# 1_Battery.net
KiCad netlist of a schematic drawn in Altium Designer
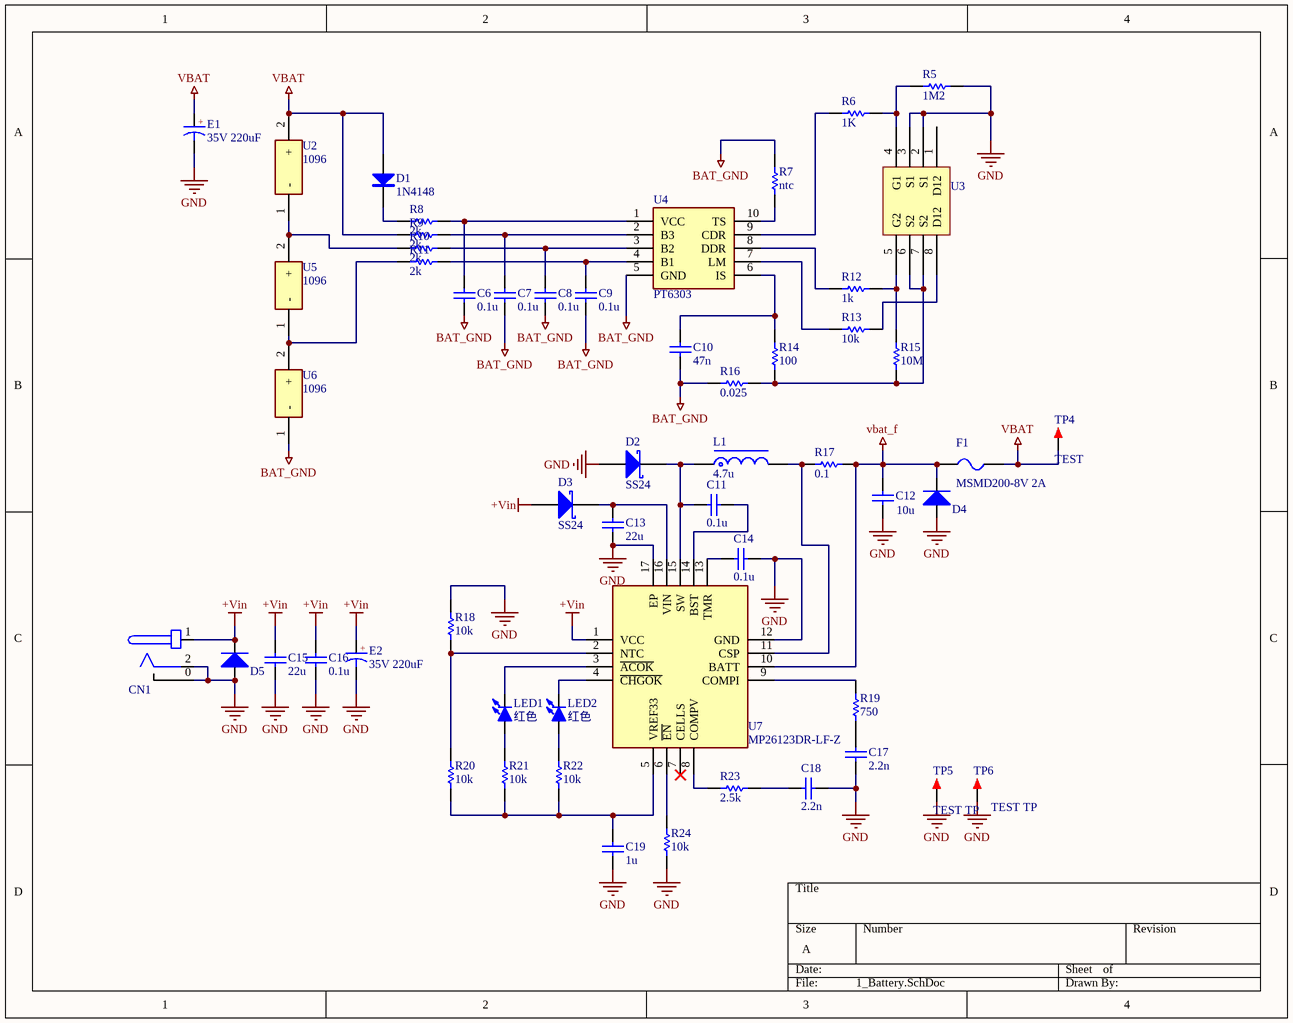
[diagram p0: 1_Battery.SchDoc]

(export (version "E")
  (design (tool "Eeschema 10.0.6"))
  (components
    (comp (ref "C6")
      (value "0.1u")
      (footprint "CAP_0603_SMD")
      (description "Capacitor, 0603, SMD")
      (fields (field (name "PUBLISHER") "Altium Limited"))
      (libsource (lib "myRLC") (part "CAP_0603_SMD"))
    )
    (comp (ref "C7")
      (value "0.1u")
      (footprint "CAP_0603_SMD")
      (description "Capacitor, 0603, SMD")
      (fields (field (name "PUBLISHER") "Altium Limited"))
      (libsource (lib "myRLC") (part "CAP_0603_SMD"))
    )
    (comp (ref "C8")
      (value "0.1u")
      (footprint "CAP_0603_SMD")
      (description "Capacitor, 0603, SMD")
      (fields (field (name "PUBLISHER") "Altium Limited"))
      (libsource (lib "myRLC") (part "CAP_0603_SMD"))
    )
    (comp (ref "C9")
      (value "0.1u")
      (footprint "CAP_0603_SMD")
      (description "Capacitor, 0603, SMD")
      (fields (field (name "PUBLISHER") "Altium Limited"))
      (libsource (lib "myRLC") (part "CAP_0603_SMD"))
    )
    (comp (ref "C10")
      (value "47n")
      (footprint "CAP_0603_SMD")
      (description "Capacitor, 0603, SMD")
      (fields (field (name "PUBLISHER") "Altium Limited"))
      (libsource (lib "myRLC") (part "CAP_0603_SMD"))
    )
    (comp (ref "C11")
      (value "0.1u")
      (footprint "CAP_0603_SMD")
      (description "Capacitor, 0603, SMD")
      (fields (field (name "PUBLISHER") "Altium Limited"))
      (libsource (lib "myRLC") (part "CAP_0603_SMD"))
    )
    (comp (ref "C12")
      (value "10u")
      (footprint "C1206_L")
      (description "贴片电容")
      (libsource (lib "0.1 - 电阻-电容-电感-电位器") (part "C"))
    )
    (comp (ref "C13")
      (value "22u")
      (footprint "C1812_L")
      (description "贴片电容")
      (libsource (lib "0.1 - 电阻-电容-电感-电位器") (part "C"))
    )
    (comp (ref "C14")
      (value "0.1u")
      (footprint "CAP_0603_SMD")
      (description "Capacitor, 0603, SMD")
      (fields (field (name "PUBLISHER") "Altium Limited"))
      (libsource (lib "myRLC") (part "CAP_0603_SMD"))
    )
    (comp (ref "C15")
      (value "22u")
      (footprint "C1812_L")
      (description "贴片电容")
      (libsource (lib "0.1 - 电阻-电容-电感-电位器") (part "C"))
    )
    (comp (ref "C16")
      (value "0.1u")
      (footprint "CAP_0603_SMD")
      (description "Capacitor, 0603, SMD")
      (fields (field (name "PUBLISHER") "Altium Limited"))
      (libsource (lib "myRLC") (part "CAP_0603_SMD"))
    )
    (comp (ref "C17")
      (value "2.2n")
      (footprint "CAP_0603_SMD")
      (description "Capacitor, 0603, SMD")
      (fields (field (name "PUBLISHER") "Altium Limited"))
      (libsource (lib "myRLC") (part "CAP_0603_SMD"))
    )
    (comp (ref "C18")
      (value "2.2n")
      (footprint "CAP_0603_SMD")
      (description "Capacitor, 0603, SMD")
      (fields (field (name "PUBLISHER") "Altium Limited"))
      (libsource (lib "myRLC") (part "CAP_0603_SMD"))
    )
    (comp (ref "C19")
      (value "1u")
      (footprint "CAP_0603_SMD")
      (description "Capacitor, 0603, SMD")
      (fields (field (name "PUBLISHER") "Altium Limited"))
      (libsource (lib "myRLC") (part "CAP_0603_SMD"))
    )
    (comp (ref "CN1")
      (value "PWR5.5x2.1_HP")
      (footprint "PWR5.5x2.1_HP")
      (description "DC Socket, 5.5x2.1, High-power")
      (libsource (lib "myConnectors") (part "PWR5.5x2.1_HP"))
    )
    (comp (ref "D1")
      (value "1N4148")
      (footprint "SOD-323")
      (description "开关二极管")
      (libsource (lib "0.2 - 二极管-TVS-整流桥") (part "1N4148"))
    )
    (comp (ref "D2")
      (value "SS24")
      (footprint "SMB")
      (description "肖特基二极管")
      (libsource (lib "0.2 - 二极管-TVS-整流桥") (part "SS24"))
    )
    (comp (ref "D3")
      (value "SS24")
      (footprint "SMB")
      (description "肖特基二极管")
      (libsource (lib "0.2 - 二极管-TVS-整流桥") (part "SS24"))
    )
    (comp (ref "D4")
      (value "TVS")
      (footprint "SMA")
      (description "TVS通用")
      (libsource (lib "0.2 - 二极管-TVS-整流桥") (part "TVS"))
    )
    (comp (ref "D5")
      (value "TVS")
      (footprint "SMA")
      (description "TVS通用")
      (libsource (lib "0.2 - 二极管-TVS-整流桥") (part "TVS"))
    )
    (comp (ref "E1")
      (value "35V 220uF")
      (footprint "CE E(8*10.2)")
      (description "贴片电解电容")
      (libsource (lib "0.1 - 电阻-电容-电感-电位器") (part "CE_SMD"))
    )
    (comp (ref "E2")
      (value "35V 220uF")
      (footprint "CE E(8*10.2)")
      (description "贴片电解电容")
      (libsource (lib "0.1 - 电阻-电容-电感-电位器") (part "CE_SMD"))
    )
    (comp (ref "F1")
      (value "MSMD200-8V 2A")
      (footprint "FU 1812")
      (description "贴片保险丝")
      (libsource (lib "0.5 - 保险丝-晶振-光耦") (part "FU"))
    )
    (comp (ref "L1")
      (value "4.7u")
      (footprint "L-SMD-0630")
      (description "一体成型电感")
      (libsource (lib "0.1 - 电阻-电容-电感-电位器") (part "L-Molding Choke"))
    )
    (comp (ref "LED1")
      (value "红色")
      (footprint "LED0603_Y")
      (description "贴片LED")
      (libsource (lib "0.3 - LED发光二极管") (part "LED-SMD"))
    )
    (comp (ref "LED2")
      (value "红色")
      (footprint "LED0603_Y")
      (description "贴片LED")
      (libsource (lib "0.3 - LED发光二极管") (part "LED-SMD"))
    )
    (comp (ref "R5")
      (value "1M2")
      (footprint "RES_0603_SMD")
      (description "Resistor, 0603, SMD")
      (fields (field (name "PUBLISHER") "Altium Limited"))
      (libsource (lib "myRLC") (part "RES_0603_SMD"))
    )
    (comp (ref "R6")
      (value "1K")
      (footprint "RES_0603_SMD")
      (description "Resistor, 0603, SMD")
      (fields (field (name "PUBLISHER") "Altium Limited"))
      (libsource (lib "myRLC") (part "RES_0603_SMD"))
    )
    (comp (ref "R7")
      (value "ntc")
      (footprint "RES_0603_SMD")
      (description "Resistor, 0603, SMD")
      (fields (field (name "PUBLISHER") "Altium Limited"))
      (libsource (lib "myRLC") (part "RES_0603_SMD"))
    )
    (comp (ref "R8")
      (value "2k")
      (footprint "RES_0603_SMD")
      (description "Resistor, 0603, SMD")
      (fields (field (name "PUBLISHER") "Altium Limited"))
      (libsource (lib "myRLC") (part "RES_0603_SMD"))
    )
    (comp (ref "R9")
      (value "2k")
      (footprint "RES_0603_SMD")
      (description "Resistor, 0603, SMD")
      (fields (field (name "PUBLISHER") "Altium Limited"))
      (libsource (lib "myRLC") (part "RES_0603_SMD"))
    )
    (comp (ref "R10")
      (value "2k")
      (footprint "RES_0603_SMD")
      (description "Resistor, 0603, SMD")
      (fields (field (name "PUBLISHER") "Altium Limited"))
      (libsource (lib "myRLC") (part "RES_0603_SMD"))
    )
    (comp (ref "R11")
      (value "2k")
      (footprint "RES_0603_SMD")
      (description "Resistor, 0603, SMD")
      (fields (field (name "PUBLISHER") "Altium Limited"))
      (libsource (lib "myRLC") (part "RES_0603_SMD"))
    )
    (comp (ref "R12")
      (value "1k")
      (footprint "RES_0603_SMD")
      (description "Resistor, 0603, SMD")
      (fields (field (name "PUBLISHER") "Altium Limited"))
      (libsource (lib "myRLC") (part "RES_0603_SMD"))
    )
    (comp (ref "R13")
      (value "10k")
      (footprint "RES_0603_SMD")
      (description "Resistor, 0603, SMD")
      (fields (field (name "PUBLISHER") "Altium Limited"))
      (libsource (lib "myRLC") (part "RES_0603_SMD"))
    )
    (comp (ref "R14")
      (value "100")
      (footprint "RES_0603_SMD")
      (description "Resistor, 0603, SMD")
      (fields (field (name "PUBLISHER") "Altium Limited"))
      (libsource (lib "myRLC") (part "RES_0603_SMD"))
    )
    (comp (ref "R15")
      (value "10M")
      (footprint "RES_0603_SMD")
      (description "Resistor, 0603, SMD")
      (fields (field (name "PUBLISHER") "Altium Limited"))
      (libsource (lib "myRLC") (part "RES_0603_SMD"))
    )
    (comp (ref "R16")
      (value "0.025")
      (footprint "RES_1206_SMD")
      (description "Resistor, 1206, SMD")
      (fields (field (name "PUBLISHER") "Altium Limited"))
      (libsource (lib "myRLC") (part "RES_1206_SMD"))
    )
    (comp (ref "R17")
      (value "0.1")
      (footprint "RES_1206_SMD")
      (description "Resistor, 1206, SMD")
      (fields (field (name "PUBLISHER") "Altium Limited"))
      (libsource (lib "myRLC") (part "RES_1206_SMD"))
    )
    (comp (ref "R18")
      (value "10k")
      (footprint "RES_0603_SMD")
      (description "Resistor, 0603, SMD")
      (fields (field (name "PUBLISHER") "Altium Limited"))
      (libsource (lib "myRLC") (part "RES_0603_SMD"))
    )
    (comp (ref "R19")
      (value "750")
      (footprint "RES_0603_SMD")
      (description "Resistor, 0603, SMD")
      (fields (field (name "PUBLISHER") "Altium Limited"))
      (libsource (lib "myRLC") (part "RES_0603_SMD"))
    )
    (comp (ref "R20")
      (value "10k")
      (footprint "RES_0603_SMD")
      (description "Resistor, 0603, SMD")
      (fields (field (name "PUBLISHER") "Altium Limited"))
      (libsource (lib "myRLC") (part "RES_0603_SMD"))
    )
    (comp (ref "R21")
      (value "10k")
      (footprint "RES_0603_SMD")
      (description "Resistor, 0603, SMD")
      (fields (field (name "PUBLISHER") "Altium Limited"))
      (libsource (lib "myRLC") (part "RES_0603_SMD"))
    )
    (comp (ref "R22")
      (value "10k")
      (footprint "RES_0603_SMD")
      (description "Resistor, 0603, SMD")
      (fields (field (name "PUBLISHER") "Altium Limited"))
      (libsource (lib "myRLC") (part "RES_0603_SMD"))
    )
    (comp (ref "R23")
      (value "2.5k")
      (footprint "RES_0603_SMD")
      (description "Resistor, 0603, SMD")
      (fields (field (name "PUBLISHER") "Altium Limited"))
      (libsource (lib "myRLC") (part "RES_0603_SMD"))
    )
    (comp (ref "R24")
      (value "10k")
      (footprint "RES_0603_SMD")
      (description "Resistor, 0603, SMD")
      (fields (field (name "PUBLISHER") "Altium Limited"))
      (libsource (lib "myRLC") (part "RES_0603_SMD"))
    )
    (comp (ref "TP4")
      (value "TEST")
      (footprint "TEST 1.2")
      (description "测试点")
      (libsource (lib "0.7 - 常用按键-开关-蜂鸣器-电池-测试点") (part "TEST"))
    )
    (comp (ref "TP5")
      (value "TEST TP")
      (footprint "TEST TP1.4_BK")
      (description "测试环")
      (libsource (lib "0.7 - 常用按键-开关-蜂鸣器-电池-测试点") (part "TEST TP"))
    )
    (comp (ref "TP6")
      (value "TEST TP")
      (footprint "TEST TP1.4_BK")
      (description "测试环")
      (libsource (lib "0.7 - 常用按键-开关-蜂鸣器-电池-测试点") (part "TEST TP"))
    )
    (comp (ref "U2")
      (value "1096")
      (footprint "TKY:1096")
      (description "Undefined or Miscellaneous")
      (fields (field (name "MOUSER PART NUMBER") "534-1096"))
      (libsource (lib "") (part "1096_1"))
    )
    (comp (ref "U3")
      (value "FS8205A TSSOP-8")
      (footprint "IC_TSSOP-8")
      (description "Dual N-Channel Enhancement Mode Power MOSFET")
      (libsource (lib "myICs") (part "FS8205A TSSOP-8"))
    )
    (comp (ref "U4")
      (value "PT6303")
      (footprint "TKY:SOP50P490X110-10N")
      (description "Integrated Circuit")
      (fields (field (name "ARROW PART NUMBER") "AD4001BRMZ"))
      (libsource (lib "TKY") (part "PT6303"))
    )
    (comp (ref "U5")
      (value "1096")
      (footprint "TKY:1096")
      (description "Undefined or Miscellaneous")
      (fields (field (name "MOUSER PART NUMBER") "534-1096"))
      (libsource (lib "TKY") (part "1096"))
    )
    (comp (ref "U6")
      (value "1096")
      (footprint "TKY:1096")
      (description "Undefined or Miscellaneous")
      (fields (field (name "MOUSER PART NUMBER") "534-1096"))
      (libsource (lib "TKY") (part "1096"))
    )
    (comp (ref "U7")
      (value "MP26123DR-LF-Z")
      (footprint "TKY:QFN65P400X400X100-17N-D")
      (description "Integrated Circuit")
      (fields (field (name "MOUSER PART NUMBER") "946-MP26123DRLFZ"))
      (libsource (lib "TKY") (part "MP26123DR-LF-Z"))
    )
  )
  (nets
    (net (code "1") (name "+Vin") (class "Default")
      (node (ref "C15") (pin "2") (pinfunction "2_2") (pintype "passive"))
      (node (ref "C16") (pin "2") (pinfunction "2_2") (pintype "passive"))
      (node (ref "CN1") (pin "1") (pinfunction "+_1") (pintype "passive"))
      (node (ref "D3") (pin "1") (pinfunction "A_1") (pintype "passive"))
      (node (ref "D5") (pin "2") (pinfunction "K_2") (pintype "passive"))
      (node (ref "E2") (pin "1") (pinfunction "1_1") (pintype "passive"))
      (node (ref "U7") (pin "1") (pinfunction "VCC_1") (pintype "passive"))
    )
    (net (code "2") (name "BAT_GND") (class "Default")
      (node (ref "C10") (pin "2") (pinfunction "2_2") (pintype "passive"))
      (node (ref "C6") (pin "2") (pinfunction "2_2") (pintype "passive"))
      (node (ref "C7") (pin "2") (pinfunction "2_2") (pintype "passive"))
      (node (ref "C8") (pin "2") (pinfunction "2_2") (pintype "passive"))
      (node (ref "C9") (pin "2") (pinfunction "2_2") (pintype "passive"))
      (node (ref "R16") (pin "1") (pinfunction "1_1") (pintype "passive"))
      (node (ref "R7") (pin "1") (pinfunction "1_1") (pintype "passive"))
      (node (ref "U4") (pin "5") (pinfunction "GND_5") (pintype "passive"))
      (node (ref "U6") (pin "1") (pinfunction "-_1") (pintype "passive"))
    )
    (net (code "3") (name "GND") (class "Default")
      (node (ref "C12") (pin "1") (pinfunction "1_1") (pintype "passive"))
      (node (ref "C13") (pin "1") (pinfunction "1_1") (pintype "passive"))
      (node (ref "C14") (pin "2") (pinfunction "2_2") (pintype "passive"))
      (node (ref "C15") (pin "1") (pinfunction "1_1") (pintype "passive"))
      (node (ref "C16") (pin "1") (pinfunction "1_1") (pintype "passive"))
      (node (ref "C17") (pin "1") (pinfunction "1_1") (pintype "passive"))
      (node (ref "C18") (pin "1") (pinfunction "1_1") (pintype "passive"))
      (node (ref "C19") (pin "2") (pinfunction "2_2") (pintype "passive"))
      (node (ref "CN1") (pin "0") (pinfunction "SHIELD_0") (pintype "passive"))
      (node (ref "CN1") (pin "2") (pinfunction "GND_2") (pintype "passive"))
      (node (ref "D2") (pin "1") (pinfunction "A_1") (pintype "passive"))
      (node (ref "D4") (pin "1") (pinfunction "A_1") (pintype "passive"))
      (node (ref "D5") (pin "1") (pinfunction "A_1") (pintype "passive"))
      (node (ref "E1") (pin "2") (pinfunction "2_2") (pintype "passive"))
      (node (ref "E2") (pin "2") (pinfunction "2_2") (pintype "passive"))
      (node (ref "R18") (pin "2") (pinfunction "2_2") (pintype "passive"))
      (node (ref "R24") (pin "2") (pinfunction "2_2") (pintype "passive"))
      (node (ref "R5") (pin "1") (pinfunction "1_1") (pintype "passive"))
      (node (ref "TP5") (pin "1") (pinfunction "1_1") (pintype "passive"))
      (node (ref "TP6") (pin "1") (pinfunction "1_1") (pintype "passive"))
      (node (ref "U3") (pin "2") (pinfunction "S1_2") (pintype "passive"))
      (node (ref "U3") (pin "3") (pinfunction "S1_3") (pintype "passive"))
      (node (ref "U7") (pin "12") (pinfunction "GND_12") (pintype "passive"))
      (node (ref "U7") (pin "17") (pinfunction "EP_17") (pintype "passive"))
    )
    (net (code "4") (name "Net-(C17-Pad2)") (class "Default")
      (node (ref "C17") (pin "2") (pinfunction "2_2") (pintype "passive"))
      (node (ref "R19") (pin "2") (pinfunction "2_2") (pintype "passive"))
    )
    (net (code "5") (name "Net-(C18-Pad2)") (class "Default")
      (node (ref "C18") (pin "2") (pinfunction "2_2") (pintype "passive"))
      (node (ref "R23") (pin "1") (pinfunction "1_1") (pintype "passive"))
    )
    (net (code "6") (name "Net-(D1-K)") (class "Default")
      (node (ref "D1") (pin "2") (pinfunction "K_2") (pintype "passive"))
      (node (ref "R8") (pin "2") (pinfunction "2_2") (pintype "passive"))
    )
    (net (code "7") (name "Net-(D2-K)") (class "Default")
      (node (ref "C11") (pin "1") (pinfunction "1_1") (pintype "passive"))
      (node (ref "D2") (pin "2") (pinfunction "K_2") (pintype "passive"))
      (node (ref "L1") (pin "1") (pinfunction "1_1") (pintype "passive"))
      (node (ref "U7") (pin "15") (pinfunction "SW_15") (pintype "passive"))
    )
    (net (code "8") (name "Net-(D3-K)") (class "Default")
      (node (ref "C13") (pin "2") (pinfunction "2_2") (pintype "passive"))
      (node (ref "D3") (pin "2") (pinfunction "K_2") (pintype "passive"))
      (node (ref "U7") (pin "16") (pinfunction "VIN_16") (pintype "passive"))
    )
    (net (code "9") (name "Net-(LED1-A)") (class "Default")
      (node (ref "LED1") (pin "1") (pinfunction "A_1") (pintype "passive"))
      (node (ref "R21") (pin "2") (pinfunction "2_2") (pintype "passive"))
    )
    (net (code "10") (name "Net-(LED1-K)") (class "Default")
      (node (ref "LED1") (pin "2") (pinfunction "K_2") (pintype "passive"))
      (node (ref "U7") (pin "3") (pinfunction "~{ACOK}_3") (pintype "passive"))
    )
    (net (code "11") (name "Net-(LED2-A)") (class "Default")
      (node (ref "LED2") (pin "1") (pinfunction "A_1") (pintype "passive"))
      (node (ref "R22") (pin "2") (pinfunction "2_2") (pintype "passive"))
    )
    (net (code "12") (name "Net-(LED2-K)") (class "Default")
      (node (ref "LED2") (pin "2") (pinfunction "K_2") (pintype "passive"))
      (node (ref "U7") (pin "4") (pinfunction "~{CHGOK}_4") (pintype "passive"))
    )
    (net (code "13") (name "Net-(R13-Pad1)") (class "Default")
      (node (ref "R13") (pin "1") (pinfunction "1_1") (pintype "passive"))
      (node (ref "U3") (pin "8") (pinfunction "D12_8") (pintype "passive"))
    )
    (net (code "14") (name "Net-(R14-Pad2)") (class "Default")
      (node (ref "R14") (pin "2") (pinfunction "2_2") (pintype "passive"))
      (node (ref "R15") (pin "2") (pinfunction "2_2") (pintype "passive"))
      (node (ref "R16") (pin "2") (pinfunction "2_2") (pintype "passive"))
      (node (ref "U3") (pin "6") (pinfunction "S2_6") (pintype "passive"))
      (node (ref "U3") (pin "7") (pinfunction "S2_7") (pintype "passive"))
    )
    (net (code "15") (name "Net-(U2--)") (class "Default")
      (node (ref "R10") (pin "2") (pinfunction "2_2") (pintype "passive"))
      (node (ref "U2") (pin "1") (pinfunction "-_1") (pintype "passive"))
      (node (ref "U5") (pin "2") (pinfunction "+_2") (pintype "passive"))
    )
    (net (code "16") (name "Net-(U3-G1)") (class "Default")
      (node (ref "R5") (pin "2") (pinfunction "2_2") (pintype "passive"))
      (node (ref "R6") (pin "1") (pinfunction "1_1") (pintype "passive"))
      (node (ref "U3") (pin "4") (pinfunction "G1_4") (pintype "passive"))
    )
    (net (code "17") (name "Net-(U3-G2)") (class "Default")
      (node (ref "R12") (pin "1") (pinfunction "1_1") (pintype "passive"))
      (node (ref "R15") (pin "1") (pinfunction "1_1") (pintype "passive"))
      (node (ref "U3") (pin "5") (pinfunction "G2_5") (pintype "passive"))
    )
    (net (code "18") (name "Net-(U4-B1)") (class "Default")
      (node (ref "C9") (pin "1") (pinfunction "1_1") (pintype "passive"))
      (node (ref "R11") (pin "1") (pinfunction "1_1") (pintype "passive"))
      (node (ref "U4") (pin "4") (pinfunction "B1_4") (pintype "passive"))
    )
    (net (code "19") (name "Net-(U4-B2)") (class "Default")
      (node (ref "C8") (pin "1") (pinfunction "1_1") (pintype "passive"))
      (node (ref "R10") (pin "1") (pinfunction "1_1") (pintype "passive"))
      (node (ref "U4") (pin "3") (pinfunction "B2_3") (pintype "passive"))
    )
    (net (code "20") (name "Net-(U4-B3)") (class "Default")
      (node (ref "C7") (pin "1") (pinfunction "1_1") (pintype "passive"))
      (node (ref "R9") (pin "1") (pinfunction "1_1") (pintype "passive"))
      (node (ref "U4") (pin "2") (pinfunction "B3_2") (pintype "passive"))
    )
    (net (code "21") (name "Net-(U4-CDR)") (class "Default")
      (node (ref "R6") (pin "2") (pinfunction "2_2") (pintype "passive"))
      (node (ref "U4") (pin "9") (pinfunction "CDR_9") (pintype "passive"))
    )
    (net (code "22") (name "Net-(U4-DDR)") (class "Default")
      (node (ref "R12") (pin "2") (pinfunction "2_2") (pintype "passive"))
      (node (ref "U4") (pin "8") (pinfunction "DDR_8") (pintype "passive"))
    )
    (net (code "23") (name "Net-(U4-IS)") (class "Default")
      (node (ref "C10") (pin "1") (pinfunction "1_1") (pintype "passive"))
      (node (ref "R14") (pin "1") (pinfunction "1_1") (pintype "passive"))
      (node (ref "U4") (pin "6") (pinfunction "IS_6") (pintype "passive"))
    )
    (net (code "24") (name "Net-(U4-LM)") (class "Default")
      (node (ref "R13") (pin "2") (pinfunction "2_2") (pintype "passive"))
      (node (ref "U4") (pin "7") (pinfunction "LM_7") (pintype "passive"))
    )
    (net (code "25") (name "Net-(U4-TS)") (class "Default")
      (node (ref "R7") (pin "2") (pinfunction "2_2") (pintype "passive"))
      (node (ref "U4") (pin "10") (pinfunction "TS_10") (pintype "passive"))
    )
    (net (code "26") (name "Net-(U4-VCC)") (class "Default")
      (node (ref "C6") (pin "1") (pinfunction "1_1") (pintype "passive"))
      (node (ref "R8") (pin "1") (pinfunction "1_1") (pintype "passive"))
      (node (ref "U4") (pin "1") (pinfunction "VCC_1") (pintype "passive"))
    )
    (net (code "27") (name "Net-(U5--)") (class "Default")
      (node (ref "R11") (pin "2") (pinfunction "2_2") (pintype "passive"))
      (node (ref "U5") (pin "1") (pinfunction "-_1") (pintype "passive"))
      (node (ref "U6") (pin "2") (pinfunction "+_2") (pintype "passive"))
    )
    (net (code "28") (name "Net-(U7-BST)") (class "Default")
      (node (ref "C11") (pin "2") (pinfunction "2_2") (pintype "passive"))
      (node (ref "U7") (pin "14") (pinfunction "BST_14") (pintype "passive"))
    )
    (net (code "29") (name "Net-(U7-COMPI)") (class "Default")
      (node (ref "R19") (pin "1") (pinfunction "1_1") (pintype "passive"))
      (node (ref "U7") (pin "9") (pinfunction "COMPI_9") (pintype "passive"))
    )
    (net (code "30") (name "Net-(U7-COMPV)") (class "Default")
      (node (ref "R23") (pin "2") (pinfunction "2_2") (pintype "passive"))
      (node (ref "U7") (pin "8") (pinfunction "COMPV_8") (pintype "passive"))
    )
    (net (code "31") (name "Net-(U7-CSP)") (class "Default")
      (node (ref "L1") (pin "2") (pinfunction "2_2") (pintype "passive"))
      (node (ref "R17") (pin "1") (pinfunction "1_1") (pintype "passive"))
      (node (ref "U7") (pin "11") (pinfunction "CSP_11") (pintype "passive"))
    )
    (net (code "32") (name "Net-(U7-NTC)") (class "Default")
      (node (ref "R18") (pin "1") (pinfunction "1_1") (pintype "passive"))
      (node (ref "R20") (pin "2") (pinfunction "2_2") (pintype "passive"))
      (node (ref "U7") (pin "2") (pinfunction "NTC_2") (pintype "passive"))
    )
    (net (code "33") (name "Net-(U7-TMR)") (class "Default")
      (node (ref "C14") (pin "1") (pinfunction "1_1") (pintype "passive"))
      (node (ref "U7") (pin "13") (pinfunction "TMR_13") (pintype "passive"))
    )
    (net (code "34") (name "Net-(U7-VREF33)") (class "Default")
      (node (ref "C19") (pin "1") (pinfunction "1_1") (pintype "passive"))
      (node (ref "R20") (pin "1") (pinfunction "1_1") (pintype "passive"))
      (node (ref "R21") (pin "1") (pinfunction "1_1") (pintype "passive"))
      (node (ref "R22") (pin "1") (pinfunction "1_1") (pintype "passive"))
      (node (ref "U7") (pin "5") (pinfunction "VREF33_5") (pintype "passive"))
    )
    (net (code "35") (name "Net-(U7-~{EN})") (class "Default")
      (node (ref "R24") (pin "1") (pinfunction "1_1") (pintype "passive"))
      (node (ref "U7") (pin "6") (pinfunction "~{EN}_6") (pintype "passive"))
    )
    (net (code "36") (name "VBAT") (class "Default")
      (node (ref "D1") (pin "1") (pinfunction "A_1") (pintype "passive"))
      (node (ref "E1") (pin "1") (pinfunction "1_1") (pintype "passive"))
      (node (ref "F1") (pin "2") (pinfunction "2_2") (pintype "passive"))
      (node (ref "R9") (pin "2") (pinfunction "2_2") (pintype "passive"))
      (node (ref "TP4") (pin "1") (pinfunction "1_1") (pintype "passive"))
      (node (ref "U2") (pin "2") (pinfunction "+_2") (pintype "passive"))
    )
    (net (code "37") (name "unconnected-(U3-D12-Pad1)") (class "Default")
      (node (ref "U3") (pin "1") (pinfunction "D12_1") (pintype "passive"))
    )
    (net (code "38") (name "unconnected-(U7-CELLS-Pad7)") (class "Default")
      (node (ref "U7") (pin "7") (pinfunction "CELLS_7") (pintype "passive+no_connect"))
    )
    (net (code "39") (name "vbat_f") (class "Default")
      (node (ref "C12") (pin "2") (pinfunction "2_2") (pintype "passive"))
      (node (ref "D4") (pin "2") (pinfunction "K_2") (pintype "passive"))
      (node (ref "F1") (pin "1") (pinfunction "1_1") (pintype "passive"))
      (node (ref "R17") (pin "2") (pinfunction "2_2") (pintype "passive"))
      (node (ref "U7") (pin "10") (pinfunction "BATT_10") (pintype "passive"))
    )
  )
)
